# Wireless.net
KiCad netlist of a schematic drawn in Altium Designer
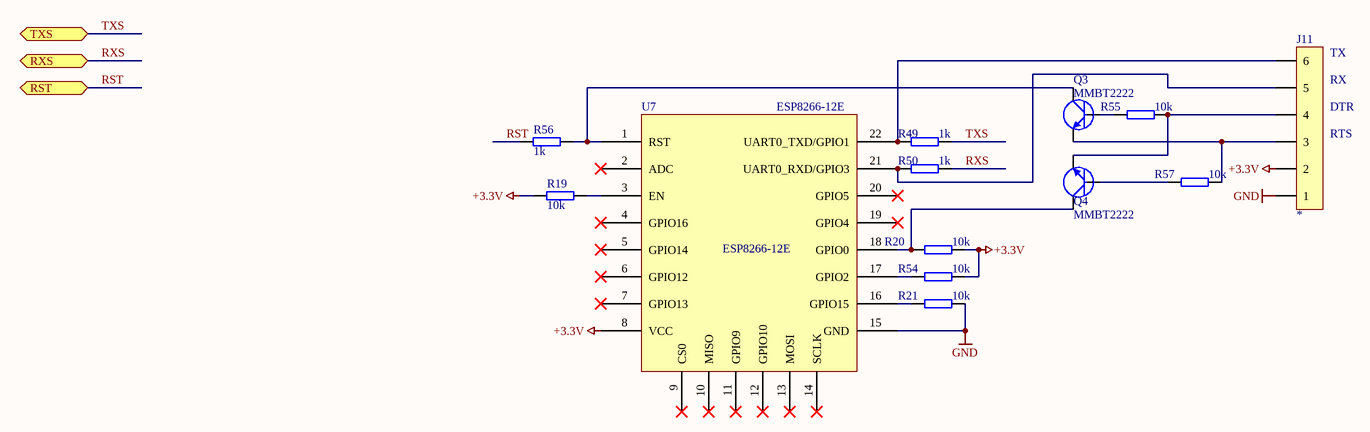
[diagram p0: Wireless.SchDoc]

(export (version "E")
  (design (tool "Eeschema 10.0.6"))
  (components
    (comp (ref "J11")
      (value "*")
      (footprint "SIL6")
      (description "6 PIN HEADER")
      (libsource (lib "SCH_LIB") (part "HEADER6"))
    )
    (comp (ref "Q3")
      (value "MMBT2222")
      (footprint "SOT23")
      (description "NPN transistor, SO23")
      (libsource (lib "SCH_LIB") (part "MMBT2222"))
    )
    (comp (ref "Q4")
      (value "MMBT2222")
      (footprint "SOT23")
      (description "NPN transistor, SO23")
      (libsource (lib "SCH_LIB") (part "MMBT2222"))
    )
    (comp (ref "R19")
      (value "10k")
      (footprint "RES 0805")
      (description "RESISTOR")
      (libsource (lib "SCH_LIB") (part "RES"))
    )
    (comp (ref "R20")
      (value "10k")
      (footprint "RES 0805")
      (description "RESISTOR")
      (libsource (lib "SCH_LIB") (part "RES"))
    )
    (comp (ref "R21")
      (value "10k")
      (footprint "RES 0805")
      (description "RESISTOR")
      (libsource (lib "SCH_LIB") (part "RES"))
    )
    (comp (ref "R49")
      (value "1k")
      (footprint "RES 0805")
      (description "RESISTOR")
      (libsource (lib "SCH_LIB") (part "RES"))
    )
    (comp (ref "R50")
      (value "1k")
      (footprint "RES 0805")
      (description "RESISTOR")
      (libsource (lib "SCH_LIB") (part "RES"))
    )
    (comp (ref "R54")
      (value "10k")
      (footprint "RES 0805")
      (description "RESISTOR")
      (libsource (lib "SCH_LIB") (part "RES"))
    )
    (comp (ref "R55")
      (value "10k")
      (footprint "RES 0805")
      (description "RESISTOR")
      (libsource (lib "SCH_LIB") (part "RES"))
    )
    (comp (ref "R56")
      (value "1k")
      (footprint "RES 0805")
      (description "RESISTOR")
      (libsource (lib "SCH_LIB") (part "RES"))
    )
    (comp (ref "R57")
      (value "10k")
      (footprint "RES 0805")
      (description "RESISTOR")
      (libsource (lib "SCH_LIB") (part "RES"))
    )
    (comp (ref "U7")
      (value "ESP8266-12E")
      (footprint "ESP8266-12E")
      (description "WiFi module")
      (libsource (lib "SCH_LIB") (part "ESP8266-12E"))
    )
  )
  (nets
    (net (code "1") (name "+3.3V") (class "Default")
      (node (ref "J11") (pin "2") (pinfunction "2_2") (pintype "passive"))
      (node (ref "R19") (pin "1") (pinfunction "1_1") (pintype "passive"))
      (node (ref "R20") (pin "2") (pinfunction "2_2") (pintype "passive"))
      (node (ref "R54") (pin "2") (pinfunction "2_2") (pintype "passive"))
      (node (ref "U7") (pin "8") (pinfunction "VCC_8") (pintype "passive"))
    )
    (net (code "2") (name "/RST") (class "Default")
      (node (ref "R56") (pin "1") (pinfunction "1_1") (pintype "passive"))
    )
    (net (code "3") (name "/RXS") (class "Default")
      (node (ref "R50") (pin "2") (pinfunction "2_2") (pintype "passive"))
    )
    (net (code "4") (name "/TXS") (class "Default")
      (node (ref "R49") (pin "2") (pinfunction "2_2") (pintype "passive"))
    )
    (net (code "5") (name "GND") (class "Default")
      (node (ref "J11") (pin "1") (pinfunction "1_1") (pintype "passive"))
      (node (ref "R21") (pin "2") (pinfunction "2_2") (pintype "passive"))
      (node (ref "U7") (pin "15") (pinfunction "GND_15") (pintype "passive"))
    )
    (net (code "6") (name "Net-(Q3-B)") (class "Default")
      (node (ref "Q3") (pin "1") (pinfunction "B_1") (pintype "passive"))
      (node (ref "R55") (pin "1") (pinfunction "1_1") (pintype "passive"))
    )
    (net (code "7") (name "Net-(Q3-C)") (class "Default")
      (node (ref "Q3") (pin "3") (pinfunction "C_3") (pintype "passive"))
      (node (ref "R56") (pin "2") (pinfunction "2_2") (pintype "passive"))
      (node (ref "U7") (pin "1") (pinfunction "RST_1") (pintype "passive"))
    )
    (net (code "8") (name "Net-(Q3-E)") (class "Default")
      (node (ref "J11") (pin "3") (pinfunction "3_3") (pintype "passive"))
      (node (ref "Q3") (pin "2") (pinfunction "E_2") (pintype "passive"))
      (node (ref "R57") (pin "2") (pinfunction "2_2") (pintype "passive"))
    )
    (net (code "9") (name "Net-(Q4-B)") (class "Default")
      (node (ref "Q4") (pin "1") (pinfunction "B_1") (pintype "passive"))
      (node (ref "R57") (pin "1") (pinfunction "1_1") (pintype "passive"))
    )
    (net (code "10") (name "Net-(Q4-C)") (class "Default")
      (node (ref "Q4") (pin "3") (pinfunction "C_3") (pintype "passive"))
      (node (ref "R20") (pin "1") (pinfunction "1_1") (pintype "passive"))
      (node (ref "U7") (pin "18") (pinfunction "GPIO0_18") (pintype "passive"))
    )
    (net (code "11") (name "Net-(Q4-E)") (class "Default")
      (node (ref "J11") (pin "4") (pinfunction "4_4") (pintype "passive"))
      (node (ref "Q4") (pin "2") (pinfunction "E_2") (pintype "passive"))
      (node (ref "R55") (pin "2") (pinfunction "2_2") (pintype "passive"))
    )
    (net (code "12") (name "Net-(U7-EN)") (class "Default")
      (node (ref "R19") (pin "2") (pinfunction "2_2") (pintype "passive"))
      (node (ref "U7") (pin "3") (pinfunction "EN_3") (pintype "passive"))
    )
    (net (code "13") (name "Net-(U7-GPIO2)") (class "Default")
      (node (ref "R54") (pin "1") (pinfunction "1_1") (pintype "passive"))
      (node (ref "U7") (pin "17") (pinfunction "GPIO2_17") (pintype "passive"))
    )
    (net (code "14") (name "Net-(U7-GPIO15)") (class "Default")
      (node (ref "R21") (pin "1") (pinfunction "1_1") (pintype "passive"))
      (node (ref "U7") (pin "16") (pinfunction "GPIO15_16") (pintype "passive"))
    )
    (net (code "15") (name "Net-(U7-UART0_RXD{slash}GPIO3)") (class "Default")
      (node (ref "J11") (pin "5") (pinfunction "5_5") (pintype "passive"))
      (node (ref "R50") (pin "1") (pinfunction "1_1") (pintype "passive"))
      (node (ref "U7") (pin "21") (pinfunction "UART0_RXD/GPIO3_21") (pintype "passive"))
    )
    (net (code "16") (name "Net-(U7-UART0_TXD{slash}GPIO1)") (class "Default")
      (node (ref "J11") (pin "6") (pinfunction "6_6") (pintype "passive"))
      (node (ref "R49") (pin "1") (pinfunction "1_1") (pintype "passive"))
      (node (ref "U7") (pin "22") (pinfunction "UART0_TXD/GPIO1_22") (pintype "passive"))
    )
    (net (code "17") (name "unconnected-(U7-ADC-Pad2)") (class "Default")
      (node (ref "U7") (pin "2") (pinfunction "ADC_2") (pintype "passive+no_connect"))
    )
    (net (code "18") (name "unconnected-(U7-CS0-Pad9)") (class "Default")
      (node (ref "U7") (pin "9") (pinfunction "CS0_9") (pintype "passive+no_connect"))
    )
    (net (code "19") (name "unconnected-(U7-GPIO4-Pad19)") (class "Default")
      (node (ref "U7") (pin "19") (pinfunction "GPIO4_19") (pintype "passive+no_connect"))
    )
    (net (code "20") (name "unconnected-(U7-GPIO5-Pad20)") (class "Default")
      (node (ref "U7") (pin "20") (pinfunction "GPIO5_20") (pintype "passive+no_connect"))
    )
    (net (code "21") (name "unconnected-(U7-GPIO9-Pad11)") (class "Default")
      (node (ref "U7") (pin "11") (pinfunction "GPIO9_11") (pintype "passive+no_connect"))
    )
    (net (code "22") (name "unconnected-(U7-GPIO10-Pad12)") (class "Default")
      (node (ref "U7") (pin "12") (pinfunction "GPIO10_12") (pintype "passive+no_connect"))
    )
    (net (code "23") (name "unconnected-(U7-GPIO12-Pad6)") (class "Default")
      (node (ref "U7") (pin "6") (pinfunction "GPIO12_6") (pintype "passive+no_connect"))
    )
    (net (code "24") (name "unconnected-(U7-GPIO13-Pad7)") (class "Default")
      (node (ref "U7") (pin "7") (pinfunction "GPIO13_7") (pintype "passive+no_connect"))
    )
    (net (code "25") (name "unconnected-(U7-GPIO14-Pad5)") (class "Default")
      (node (ref "U7") (pin "5") (pinfunction "GPIO14_5") (pintype "passive+no_connect"))
    )
    (net (code "26") (name "unconnected-(U7-GPIO16-Pad4)") (class "Default")
      (node (ref "U7") (pin "4") (pinfunction "GPIO16_4") (pintype "passive+no_connect"))
    )
    (net (code "27") (name "unconnected-(U7-MISO-Pad10)") (class "Default")
      (node (ref "U7") (pin "10") (pinfunction "MISO_10") (pintype "passive+no_connect"))
    )
    (net (code "28") (name "unconnected-(U7-MOSI-Pad13)") (class "Default")
      (node (ref "U7") (pin "13") (pinfunction "MOSI_13") (pintype "passive+no_connect"))
    )
    (net (code "29") (name "unconnected-(U7-SCLK-Pad14)") (class "Default")
      (node (ref "U7") (pin "14") (pinfunction "SCLK_14") (pintype "passive+no_connect"))
    )
  )
)
